# arm_driver.net
KiCad netlist of a schematic drawn in EAGLE
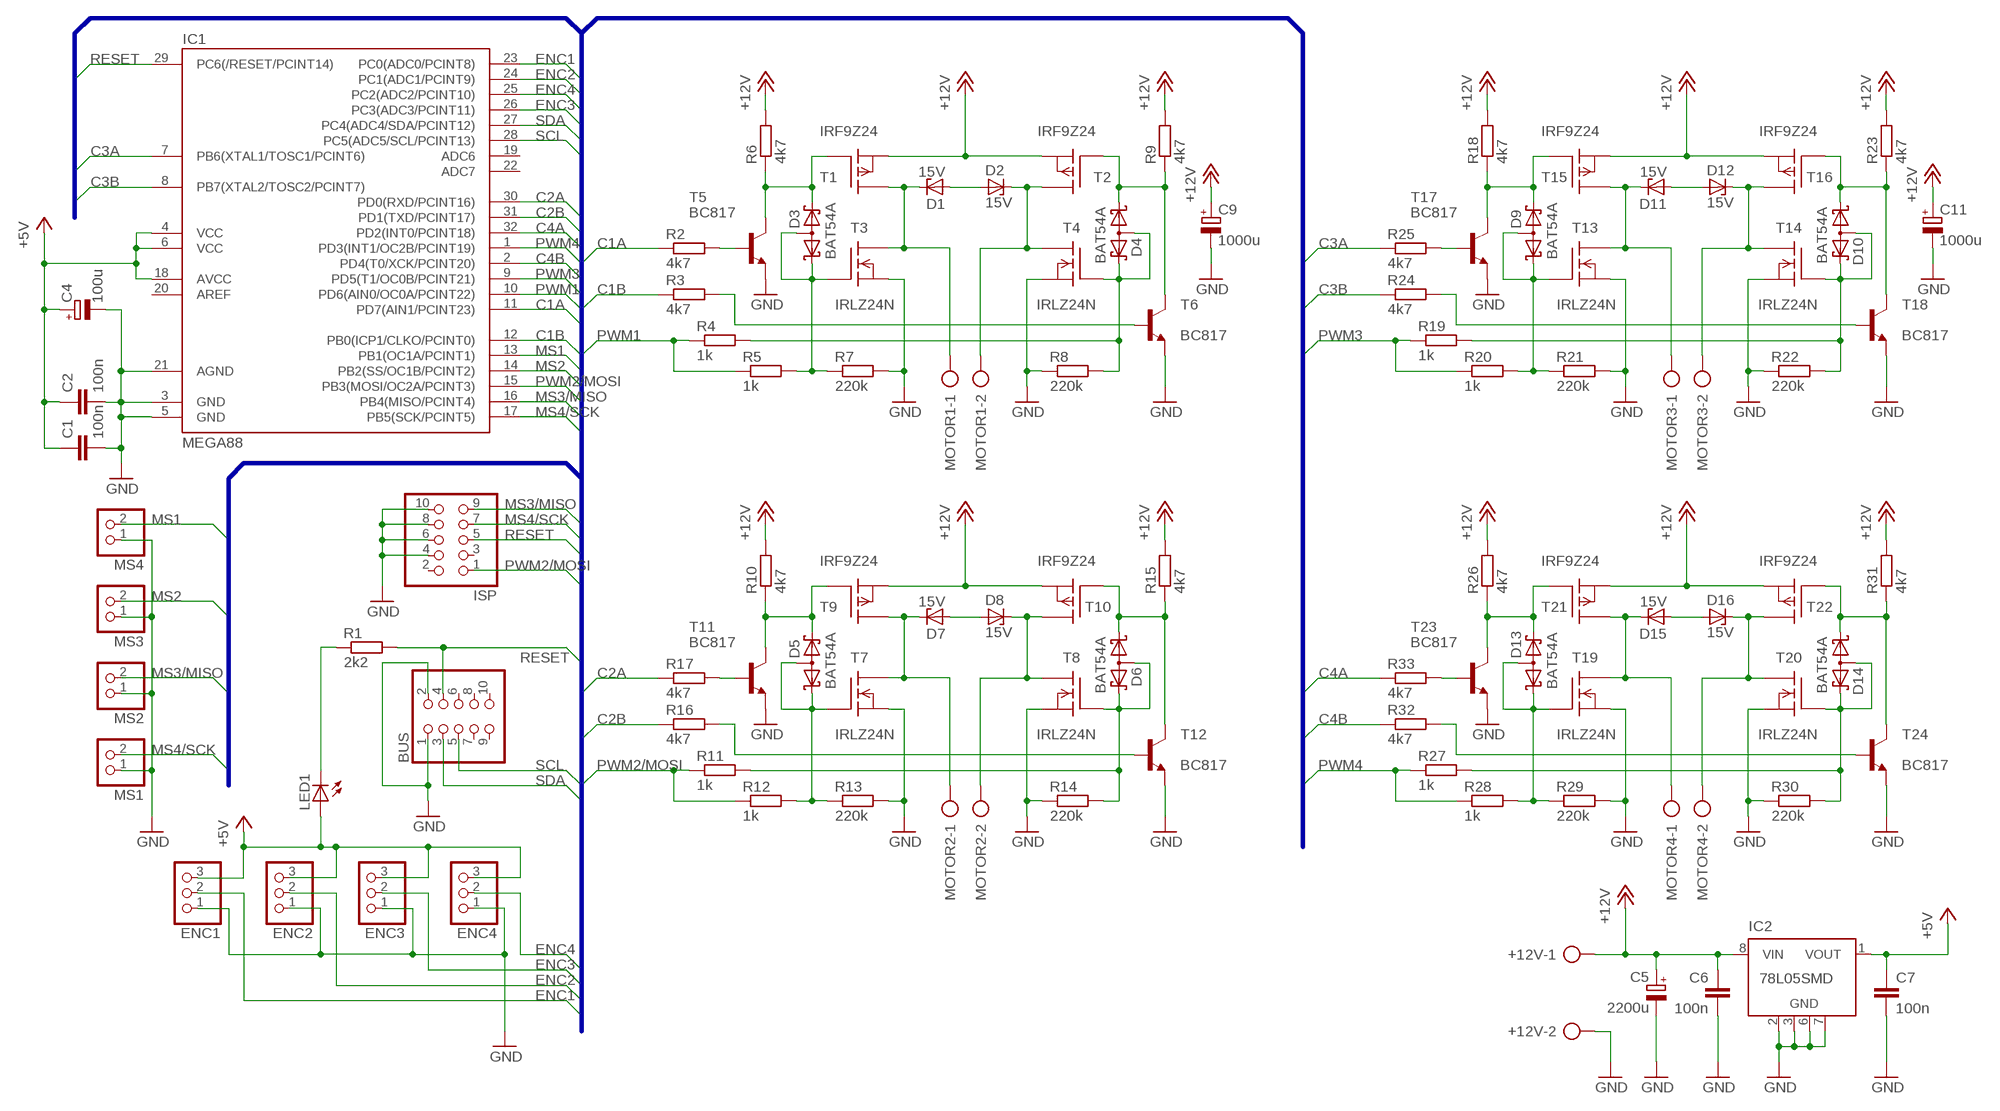
[diagram p0: schematic, sheet 1]

(export (version "E")
  (design (tool "Eeschema 10.0.6"))
  (components
    (comp (ref "+12V")
      (value "AK500/2")
      (footprint "eagle-import:AK500_2")
      (libsource (lib "eagle-import") (part "AK500/2"))
    )
    (comp (ref "BUS")
      (value "PINHD-2X5")
      (footprint "eagle-import:2X05")
      (libsource (lib "eagle-import") (part "PINHD-2X5"))
    )
    (comp (ref "C1")
      (value "100n")
      (footprint "eagle-import:C1206")
      (libsource (lib "eagle-import") (part "C-EUC1206"))
    )
    (comp (ref "C2")
      (value "100n")
      (footprint "eagle-import:C1206")
      (libsource (lib "eagle-import") (part "C-EUC1206"))
    )
    (comp (ref "C4")
      (value "100u")
      (footprint "eagle-import:D_7343-31R")
      (libsource (lib "eagle-import") (part "CPOL-EUD/7343-31R"))
    )
    (comp (ref "C5")
      (value "2200u")
      (footprint "eagle-import:E7,5-16")
      (libsource (lib "eagle-import") (part "CPOL-EUE7.5-16"))
    )
    (comp (ref "C6")
      (value "100n")
      (footprint "eagle-import:C1206")
      (libsource (lib "eagle-import") (part "C-EUC1206"))
    )
    (comp (ref "C7")
      (value "100n")
      (footprint "eagle-import:C1206")
      (libsource (lib "eagle-import") (part "C-EUC1206"))
    )
    (comp (ref "C9")
      (value "1000u")
      (footprint "eagle-import:E5-13")
      (libsource (lib "eagle-import") (part "CPOL-EUE5-13"))
    )
    (comp (ref "C11")
      (value "1000u")
      (footprint "eagle-import:E5-13")
      (libsource (lib "eagle-import") (part "CPOL-EUE5-13"))
    )
    (comp (ref "D1")
      (value "15V")
      (footprint "eagle-import:SOD80C")
      (libsource (lib "eagle-import") (part "ZENER-DIODESOD80C"))
    )
    (comp (ref "D2")
      (value "15V")
      (footprint "eagle-import:SOD80C")
      (libsource (lib "eagle-import") (part "ZENER-DIODESOD80C"))
    )
    (comp (ref "D3")
      (value "BAT54A")
      (footprint "eagle-import:SOT23")
      (libsource (lib "eagle-import") (part "BAT54A"))
    )
    (comp (ref "D4")
      (value "BAT54A")
      (footprint "eagle-import:SOT23")
      (libsource (lib "eagle-import") (part "BAT54A"))
    )
    (comp (ref "D5")
      (value "BAT54A")
      (footprint "eagle-import:SOT23")
      (libsource (lib "eagle-import") (part "BAT54A"))
    )
    (comp (ref "D6")
      (value "BAT54A")
      (footprint "eagle-import:SOT23")
      (libsource (lib "eagle-import") (part "BAT54A"))
    )
    (comp (ref "D7")
      (value "15V")
      (footprint "eagle-import:SOD80C")
      (libsource (lib "eagle-import") (part "ZENER-DIODESOD80C"))
    )
    (comp (ref "D8")
      (value "15V")
      (footprint "eagle-import:SOD80C")
      (libsource (lib "eagle-import") (part "ZENER-DIODESOD80C"))
    )
    (comp (ref "D9")
      (value "BAT54A")
      (footprint "eagle-import:SOT23")
      (libsource (lib "eagle-import") (part "BAT54A"))
    )
    (comp (ref "D10")
      (value "BAT54A")
      (footprint "eagle-import:SOT23")
      (libsource (lib "eagle-import") (part "BAT54A"))
    )
    (comp (ref "D11")
      (value "15V")
      (footprint "eagle-import:SOD80C")
      (libsource (lib "eagle-import") (part "ZENER-DIODESOD80C"))
    )
    (comp (ref "D12")
      (value "15V")
      (footprint "eagle-import:SOD80C")
      (libsource (lib "eagle-import") (part "ZENER-DIODESOD80C"))
    )
    (comp (ref "D13")
      (value "BAT54A")
      (footprint "eagle-import:SOT23")
      (libsource (lib "eagle-import") (part "BAT54A"))
    )
    (comp (ref "D14")
      (value "BAT54A")
      (footprint "eagle-import:SOT23")
      (libsource (lib "eagle-import") (part "BAT54A"))
    )
    (comp (ref "D15")
      (value "15V")
      (footprint "eagle-import:SOD80C")
      (libsource (lib "eagle-import") (part "ZENER-DIODESOD80C"))
    )
    (comp (ref "D16")
      (value "15V")
      (footprint "eagle-import:SOD80C")
      (libsource (lib "eagle-import") (part "ZENER-DIODESOD80C"))
    )
    (comp (ref "ENC1")
      (value "PINHD-1X3")
      (footprint "eagle-import:1X03")
      (libsource (lib "eagle-import") (part "PINHD-1X3"))
    )
    (comp (ref "ENC2")
      (value "PINHD-1X3")
      (footprint "eagle-import:1X03")
      (libsource (lib "eagle-import") (part "PINHD-1X3"))
    )
    (comp (ref "ENC3")
      (value "PINHD-1X3")
      (footprint "eagle-import:1X03")
      (libsource (lib "eagle-import") (part "PINHD-1X3"))
    )
    (comp (ref "ENC4")
      (value "PINHD-1X3")
      (footprint "eagle-import:1X03")
      (libsource (lib "eagle-import") (part "PINHD-1X3"))
    )
    (comp (ref "IC1")
      (value "MEGA88")
      (footprint "eagle-import:TQFP32-08")
      (libsource (lib "eagle-import") (part "MEGA48/88/168-AU"))
    )
    (comp (ref "IC2")
      (value "78L05SMD")
      (footprint "eagle-import:SO08")
      (libsource (lib "eagle-import") (part "78LSMD05"))
    )
    (comp (ref "ISP")
      (value "PINHD-2X5")
      (footprint "eagle-import:2X05")
      (libsource (lib "eagle-import") (part "PINHD-2X5"))
    )
    (comp (ref "LED1")
      (value "LEDKA-3528ASYC")
      (footprint "eagle-import:KA-3528ASYC")
      (libsource (lib "eagle-import") (part "LEDKA-3528ASYC"))
    )
    (comp (ref "MOTOR1")
      (value "AK500/2")
      (footprint "eagle-import:AK500_2")
      (libsource (lib "eagle-import") (part "AK500/2"))
    )
    (comp (ref "MOTOR2")
      (value "AK500/2")
      (footprint "eagle-import:AK500_2")
      (libsource (lib "eagle-import") (part "AK500/2"))
    )
    (comp (ref "MOTOR3")
      (value "AK500/2")
      (footprint "eagle-import:AK500_2")
      (libsource (lib "eagle-import") (part "AK500/2"))
    )
    (comp (ref "MOTOR4")
      (value "AK500/2")
      (footprint "eagle-import:AK500_2")
      (libsource (lib "eagle-import") (part "AK500/2"))
    )
    (comp (ref "MS1")
      (value "PINHD-1X2")
      (footprint "eagle-import:1X02")
      (libsource (lib "eagle-import") (part "PINHD-1X2"))
    )
    (comp (ref "MS2")
      (value "PINHD-1X2")
      (footprint "eagle-import:1X02")
      (libsource (lib "eagle-import") (part "PINHD-1X2"))
    )
    (comp (ref "MS3")
      (value "PINHD-1X2")
      (footprint "eagle-import:1X02")
      (libsource (lib "eagle-import") (part "PINHD-1X2"))
    )
    (comp (ref "MS4")
      (value "PINHD-1X2")
      (footprint "eagle-import:1X02")
      (libsource (lib "eagle-import") (part "PINHD-1X2"))
    )
    (comp (ref "R1")
      (value "2k2")
      (footprint "eagle-import:R1206")
      (libsource (lib "eagle-import") (part "R-EU_R1206"))
    )
    (comp (ref "R2")
      (value "4k7")
      (footprint "eagle-import:R1206")
      (libsource (lib "eagle-import") (part "R-EU_R1206"))
    )
    (comp (ref "R3")
      (value "4k7")
      (footprint "eagle-import:R1206")
      (libsource (lib "eagle-import") (part "R-EU_R1206"))
    )
    (comp (ref "R4")
      (value "1k")
      (footprint "eagle-import:R1206")
      (libsource (lib "eagle-import") (part "R-EU_R1206"))
    )
    (comp (ref "R5")
      (value "1k")
      (footprint "eagle-import:R1206")
      (libsource (lib "eagle-import") (part "R-EU_R1206"))
    )
    (comp (ref "R6")
      (value "4k7")
      (footprint "eagle-import:R1206")
      (libsource (lib "eagle-import") (part "R-EU_R1206"))
    )
    (comp (ref "R7")
      (value "220k")
      (footprint "eagle-import:R1206")
      (libsource (lib "eagle-import") (part "R-EU_R1206"))
    )
    (comp (ref "R8")
      (value "220k")
      (footprint "eagle-import:R1206")
      (libsource (lib "eagle-import") (part "R-EU_R1206"))
    )
    (comp (ref "R9")
      (value "4k7")
      (footprint "eagle-import:R1206")
      (libsource (lib "eagle-import") (part "R-EU_R1206"))
    )
    (comp (ref "R10")
      (value "4k7")
      (footprint "eagle-import:R1206")
      (libsource (lib "eagle-import") (part "R-EU_R1206"))
    )
    (comp (ref "R11")
      (value "1k")
      (footprint "eagle-import:R1206")
      (libsource (lib "eagle-import") (part "R-EU_R1206"))
    )
    (comp (ref "R12")
      (value "1k")
      (footprint "eagle-import:R1206")
      (libsource (lib "eagle-import") (part "R-EU_R1206"))
    )
    (comp (ref "R13")
      (value "220k")
      (footprint "eagle-import:R1206")
      (libsource (lib "eagle-import") (part "R-EU_R1206"))
    )
    (comp (ref "R14")
      (value "220k")
      (footprint "eagle-import:R1206")
      (libsource (lib "eagle-import") (part "R-EU_R1206"))
    )
    (comp (ref "R15")
      (value "4k7")
      (footprint "eagle-import:R1206")
      (libsource (lib "eagle-import") (part "R-EU_R1206"))
    )
    (comp (ref "R16")
      (value "4k7")
      (footprint "eagle-import:R1206")
      (libsource (lib "eagle-import") (part "R-EU_R1206"))
    )
    (comp (ref "R17")
      (value "4k7")
      (footprint "eagle-import:R1206")
      (libsource (lib "eagle-import") (part "R-EU_R1206"))
    )
    (comp (ref "R18")
      (value "4k7")
      (footprint "eagle-import:R1206")
      (libsource (lib "eagle-import") (part "R-EU_R1206"))
    )
    (comp (ref "R19")
      (value "1k")
      (footprint "eagle-import:R1206")
      (libsource (lib "eagle-import") (part "R-EU_R1206"))
    )
    (comp (ref "R20")
      (value "1k")
      (footprint "eagle-import:R1206")
      (libsource (lib "eagle-import") (part "R-EU_R1206"))
    )
    (comp (ref "R21")
      (value "220k")
      (footprint "eagle-import:R1206")
      (libsource (lib "eagle-import") (part "R-EU_R1206"))
    )
    (comp (ref "R22")
      (value "220k")
      (footprint "eagle-import:R1206")
      (libsource (lib "eagle-import") (part "R-EU_R1206"))
    )
    (comp (ref "R23")
      (value "4k7")
      (footprint "eagle-import:R1206")
      (libsource (lib "eagle-import") (part "R-EU_R1206"))
    )
    (comp (ref "R24")
      (value "4k7")
      (footprint "eagle-import:R1206")
      (libsource (lib "eagle-import") (part "R-EU_R1206"))
    )
    (comp (ref "R25")
      (value "4k7")
      (footprint "eagle-import:R1206")
      (libsource (lib "eagle-import") (part "R-EU_R1206"))
    )
    (comp (ref "R26")
      (value "4k7")
      (footprint "eagle-import:R1206")
      (libsource (lib "eagle-import") (part "R-EU_R1206"))
    )
    (comp (ref "R27")
      (value "1k")
      (footprint "eagle-import:R1206")
      (libsource (lib "eagle-import") (part "R-EU_R1206"))
    )
    (comp (ref "R28")
      (value "1k")
      (footprint "eagle-import:R1206")
      (libsource (lib "eagle-import") (part "R-EU_R1206"))
    )
    (comp (ref "R29")
      (value "220k")
      (footprint "eagle-import:R1206")
      (libsource (lib "eagle-import") (part "R-EU_R1206"))
    )
    (comp (ref "R30")
      (value "220k")
      (footprint "eagle-import:R1206")
      (libsource (lib "eagle-import") (part "R-EU_R1206"))
    )
    (comp (ref "R31")
      (value "4k7")
      (footprint "eagle-import:R1206")
      (libsource (lib "eagle-import") (part "R-EU_R1206"))
    )
    (comp (ref "R32")
      (value "4k7")
      (footprint "eagle-import:R1206")
      (libsource (lib "eagle-import") (part "R-EU_R1206"))
    )
    (comp (ref "R33")
      (value "4k7")
      (footprint "eagle-import:R1206")
      (libsource (lib "eagle-import") (part "R-EU_R1206"))
    )
    (comp (ref "T1")
      (value "IRF9Z24")
      (footprint "eagle-import:TO220")
      (libsource (lib "eagle-import") (part "IRF9530"))
    )
    (comp (ref "T2")
      (value "IRF9Z24")
      (footprint "eagle-import:TO220")
      (libsource (lib "eagle-import") (part "IRF9530"))
    )
    (comp (ref "T3")
      (value "IRLZ24N")
      (footprint "eagle-import:TO220")
      (libsource (lib "eagle-import") (part "IRF540"))
    )
    (comp (ref "T4")
      (value "IRLZ24N")
      (footprint "eagle-import:TO220")
      (libsource (lib "eagle-import") (part "IRF540"))
    )
    (comp (ref "T5")
      (value "BC817")
      (footprint "eagle-import:SOT23-BEC")
      (libsource (lib "eagle-import") (part "-NPN-SOT23-BECBC817-16"))
    )
    (comp (ref "T6")
      (value "BC817")
      (footprint "eagle-import:SOT23-BEC")
      (libsource (lib "eagle-import") (part "-NPN-SOT23-BECBC817-16"))
    )
    (comp (ref "T7")
      (value "IRLZ24N")
      (footprint "eagle-import:TO220")
      (libsource (lib "eagle-import") (part "IRF540"))
    )
    (comp (ref "T8")
      (value "IRLZ24N")
      (footprint "eagle-import:TO220")
      (libsource (lib "eagle-import") (part "IRF540"))
    )
    (comp (ref "T9")
      (value "IRF9Z24")
      (footprint "eagle-import:TO220")
      (libsource (lib "eagle-import") (part "IRF9530"))
    )
    (comp (ref "T10")
      (value "IRF9Z24")
      (footprint "eagle-import:TO220")
      (libsource (lib "eagle-import") (part "IRF9530"))
    )
    (comp (ref "T11")
      (value "BC817")
      (footprint "eagle-import:SOT23-BEC")
      (libsource (lib "eagle-import") (part "-NPN-SOT23-BECBC817-16"))
    )
    (comp (ref "T12")
      (value "BC817")
      (footprint "eagle-import:SOT23-BEC")
      (libsource (lib "eagle-import") (part "-NPN-SOT23-BECBC817-16"))
    )
    (comp (ref "T13")
      (value "IRLZ24N")
      (footprint "eagle-import:TO220")
      (libsource (lib "eagle-import") (part "IRF540"))
    )
    (comp (ref "T14")
      (value "IRLZ24N")
      (footprint "eagle-import:TO220")
      (libsource (lib "eagle-import") (part "IRF540"))
    )
    (comp (ref "T15")
      (value "IRF9Z24")
      (footprint "eagle-import:TO220")
      (libsource (lib "eagle-import") (part "IRF9530"))
    )
    (comp (ref "T16")
      (value "IRF9Z24")
      (footprint "eagle-import:TO220")
      (libsource (lib "eagle-import") (part "IRF9530"))
    )
    (comp (ref "T17")
      (value "BC817")
      (footprint "eagle-import:SOT23-BEC")
      (libsource (lib "eagle-import") (part "-NPN-SOT23-BECBC817-16"))
    )
    (comp (ref "T18")
      (value "BC817")
      (footprint "eagle-import:SOT23-BEC")
      (libsource (lib "eagle-import") (part "-NPN-SOT23-BECBC817-16"))
    )
    (comp (ref "T19")
      (value "IRLZ24N")
      (footprint "eagle-import:TO220")
      (libsource (lib "eagle-import") (part "IRF540"))
    )
    (comp (ref "T20")
      (value "IRLZ24N")
      (footprint "eagle-import:TO220")
      (libsource (lib "eagle-import") (part "IRF540"))
    )
    (comp (ref "T21")
      (value "IRF9Z24")
      (footprint "eagle-import:TO220")
      (libsource (lib "eagle-import") (part "IRF9530"))
    )
    (comp (ref "T22")
      (value "IRF9Z24")
      (footprint "eagle-import:TO220")
      (libsource (lib "eagle-import") (part "IRF9530"))
    )
    (comp (ref "T23")
      (value "BC817")
      (footprint "eagle-import:SOT23-BEC")
      (libsource (lib "eagle-import") (part "-NPN-SOT23-BECBC817-16"))
    )
    (comp (ref "T24")
      (value "BC817")
      (footprint "eagle-import:SOT23-BEC")
      (libsource (lib "eagle-import") (part "-NPN-SOT23-BECBC817-16"))
    )
  )
  (nets
    (net (code "1") (name "+5V") (class "Default")
      (node (ref "C1") (pin "1") (pinfunction "1_1") (pintype "passive"))
      (node (ref "C2") (pin "1") (pinfunction "1_1") (pintype "passive"))
      (node (ref "C4") (pin "+") (pinfunction "+_+") (pintype "passive"))
      (node (ref "C7") (pin "1") (pinfunction "1_1") (pintype "passive"))
      (node (ref "ENC1") (pin "3") (pinfunction "3_3") (pintype "passive"))
      (node (ref "ENC2") (pin "3") (pinfunction "3_3") (pintype "passive"))
      (node (ref "ENC3") (pin "3") (pinfunction "3_3") (pintype "passive"))
      (node (ref "ENC4") (pin "3") (pinfunction "3_3") (pintype "passive"))
      (node (ref "IC1") (pin "18") (pinfunction "AVCC_18") (pintype "passive"))
      (node (ref "IC1") (pin "4") (pinfunction "VCC_4") (pintype "power_in"))
      (node (ref "IC1") (pin "6") (pinfunction "VCC_6") (pintype "power_in"))
      (node (ref "IC2") (pin "1") (pinfunction "VOUT_1") (pintype "output"))
      (node (ref "LED1") (pin "A") (pinfunction "A_A") (pintype "passive"))
    )
    (net (code "2") (name "+12V") (class "Default")
      (node (ref "+12V") (pin "1") (pinfunction "KL_1") (pintype "passive"))
      (node (ref "C11") (pin "+") (pinfunction "+_+") (pintype "passive"))
      (node (ref "C5") (pin "+") (pinfunction "+_+") (pintype "passive"))
      (node (ref "C6") (pin "1") (pinfunction "1_1") (pintype "passive"))
      (node (ref "C9") (pin "+") (pinfunction "+_+") (pintype "passive"))
      (node (ref "IC2") (pin "8") (pinfunction "VIN_8") (pintype "passive"))
      (node (ref "R10") (pin "2") (pinfunction "2_2") (pintype "passive"))
      (node (ref "R15") (pin "2") (pinfunction "2_2") (pintype "passive"))
      (node (ref "R18") (pin "2") (pinfunction "2_2") (pintype "passive"))
      (node (ref "R23") (pin "2") (pinfunction "2_2") (pintype "passive"))
      (node (ref "R26") (pin "2") (pinfunction "2_2") (pintype "passive"))
      (node (ref "R31") (pin "2") (pinfunction "2_2") (pintype "passive"))
      (node (ref "R6") (pin "2") (pinfunction "2_2") (pintype "passive"))
      (node (ref "R9") (pin "2") (pinfunction "2_2") (pintype "passive"))
      (node (ref "T1") (pin "3") (pinfunction "S_3") (pintype "passive"))
      (node (ref "T10") (pin "3") (pinfunction "S_3") (pintype "passive"))
      (node (ref "T15") (pin "3") (pinfunction "S_3") (pintype "passive"))
      (node (ref "T16") (pin "3") (pinfunction "S_3") (pintype "passive"))
      (node (ref "T2") (pin "3") (pinfunction "S_3") (pintype "passive"))
      (node (ref "T21") (pin "3") (pinfunction "S_3") (pintype "passive"))
      (node (ref "T22") (pin "3") (pinfunction "S_3") (pintype "passive"))
      (node (ref "T9") (pin "3") (pinfunction "S_3") (pintype "passive"))
    )
    (net (code "3") (name "/C1A") (class "Default")
      (node (ref "IC1") (pin "11") (pinfunction "PD7(AIN1/PCINT23)_11") (pintype "bidirectional"))
      (node (ref "R2") (pin "1") (pinfunction "1_1") (pintype "passive"))
    )
    (net (code "4") (name "/C1B") (class "Default")
      (node (ref "IC1") (pin "12") (pinfunction "PB0(ICP1/CLKO/PCINT0)_12") (pintype "bidirectional"))
      (node (ref "R3") (pin "1") (pinfunction "1_1") (pintype "passive"))
    )
    (net (code "5") (name "/C2A") (class "Default")
      (node (ref "IC1") (pin "30") (pinfunction "PD0(RXD/PCINT16)_30") (pintype "bidirectional"))
      (node (ref "R17") (pin "1") (pinfunction "1_1") (pintype "passive"))
    )
    (net (code "6") (name "/C2B") (class "Default")
      (node (ref "IC1") (pin "31") (pinfunction "PD1(TXD/PCINT17)_31") (pintype "bidirectional"))
      (node (ref "R16") (pin "1") (pinfunction "1_1") (pintype "passive"))
    )
    (net (code "7") (name "/C3A") (class "Default")
      (node (ref "IC1") (pin "7") (pinfunction "PB6(XTAL1/TOSC1/PCINT6)_7") (pintype "bidirectional"))
      (node (ref "R25") (pin "1") (pinfunction "1_1") (pintype "passive"))
    )
    (net (code "8") (name "/C3B") (class "Default")
      (node (ref "IC1") (pin "8") (pinfunction "PB7(XTAL2/TOSC2/PCINT7)_8") (pintype "bidirectional"))
      (node (ref "R24") (pin "1") (pinfunction "1_1") (pintype "passive"))
    )
    (net (code "9") (name "/C4A") (class "Default")
      (node (ref "IC1") (pin "32") (pinfunction "PD2(INT0/PCINT18)_32") (pintype "bidirectional"))
      (node (ref "R33") (pin "1") (pinfunction "1_1") (pintype "passive"))
    )
    (net (code "10") (name "/C4B") (class "Default")
      (node (ref "IC1") (pin "2") (pinfunction "PD4(T0/XCK/PCINT20)_2") (pintype "bidirectional"))
      (node (ref "R32") (pin "1") (pinfunction "1_1") (pintype "passive"))
    )
    (net (code "11") (name "/ENC1") (class "Default")
      (node (ref "ENC1") (pin "2") (pinfunction "2_2") (pintype "passive"))
      (node (ref "IC1") (pin "23") (pinfunction "PC0(ADC0/PCINT8)_23") (pintype "bidirectional"))
    )
    (net (code "12") (name "/ENC2") (class "Default")
      (node (ref "ENC2") (pin "2") (pinfunction "2_2") (pintype "passive"))
      (node (ref "IC1") (pin "24") (pinfunction "PC1(ADC1/PCINT9)_24") (pintype "bidirectional"))
    )
    (net (code "13") (name "/ENC3") (class "Default")
      (node (ref "ENC3") (pin "2") (pinfunction "2_2") (pintype "passive"))
      (node (ref "IC1") (pin "26") (pinfunction "PC3(ADC3/PCINT11)_26") (pintype "bidirectional"))
    )
    (net (code "14") (name "/ENC4") (class "Default")
      (node (ref "ENC4") (pin "2") (pinfunction "2_2") (pintype "passive"))
      (node (ref "IC1") (pin "25") (pinfunction "PC2(ADC2/PCINT10)_25") (pintype "bidirectional"))
    )
    (net (code "15") (name "/MS1") (class "Default")
      (node (ref "IC1") (pin "13") (pinfunction "PB1(OC1A/PCINT1)_13") (pintype "bidirectional"))
      (node (ref "MS4") (pin "2") (pinfunction "2_2") (pintype "passive"))
    )
    (net (code "16") (name "/MS2") (class "Default")
      (node (ref "IC1") (pin "14") (pinfunction "PB2(SS/OC1B/PCINT2)_14") (pintype "bidirectional"))
      (node (ref "MS3") (pin "2") (pinfunction "2_2") (pintype "passive"))
    )
    (net (code "17") (name "/MS3{slash}MISO") (class "Default")
      (node (ref "IC1") (pin "16") (pinfunction "PB4(MISO/PCINT4)_16") (pintype "bidirectional"))
      (node (ref "ISP") (pin "9") (pinfunction "9_9") (pintype "passive"))
      (node (ref "MS2") (pin "2") (pinfunction "2_2") (pintype "passive"))
    )
    (net (code "18") (name "/MS4{slash}SCK") (class "Default")
      (node (ref "IC1") (pin "17") (pinfunction "PB5(SCK/PCINT5)_17") (pintype "bidirectional"))
      (node (ref "ISP") (pin "7") (pinfunction "7_7") (pintype "passive"))
      (node (ref "MS1") (pin "2") (pinfunction "2_2") (pintype "passive"))
    )
    (net (code "19") (name "/PWM1") (class "Default")
      (node (ref "IC1") (pin "10") (pinfunction "PD6(AIN0/OC0A/PCINT22)_10") (pintype "bidirectional"))
      (node (ref "R4") (pin "1") (pinfunction "1_1") (pintype "passive"))
      (node (ref "R5") (pin "1") (pinfunction "1_1") (pintype "passive"))
    )
    (net (code "20") (name "/PWM2{slash}MOSI") (class "Default")
      (node (ref "IC1") (pin "15") (pinfunction "PB3(MOSI/OC2A/PCINT3)_15") (pintype "bidirectional"))
      (node (ref "ISP") (pin "1") (pinfunction "1_1") (pintype "passive"))
      (node (ref "R11") (pin "1") (pinfunction "1_1") (pintype "passive"))
      (node (ref "R12") (pin "1") (pinfunction "1_1") (pintype "passive"))
    )
    (net (code "21") (name "/PWM3") (class "Default")
      (node (ref "IC1") (pin "9") (pinfunction "PD5(T1/OC0B/PCINT21)_9") (pintype "bidirectional"))
      (node (ref "R19") (pin "1") (pinfunction "1_1") (pintype "passive"))
      (node (ref "R20") (pin "1") (pinfunction "1_1") (pintype "passive"))
    )
    (net (code "22") (name "/PWM4") (class "Default")
      (node (ref "IC1") (pin "1") (pinfunction "PD3(INT1/OC2B/PCINT19)_1") (pintype "bidirectional"))
      (node (ref "R27") (pin "1") (pinfunction "1_1") (pintype "passive"))
      (node (ref "R28") (pin "1") (pinfunction "1_1") (pintype "passive"))
    )
    (net (code "23") (name "/RESET") (class "Default")
      (node (ref "BUS") (pin "4") (pinfunction "4_4") (pintype "passive"))
      (node (ref "IC1") (pin "29") (pinfunction "PC6(/RESET/PCINT14)_29") (pintype "bidirectional"))
      (node (ref "ISP") (pin "5") (pinfunction "5_5") (pintype "passive"))
      (node (ref "R1") (pin "2") (pinfunction "2_2") (pintype "passive"))
    )
    (net (code "24") (name "/SCL") (class "Default")
      (node (ref "BUS") (pin "5") (pinfunction "5_5") (pintype "passive"))
      (node (ref "IC1") (pin "28") (pinfunction "PC5(ADC5/SCL/PCINT13)_28") (pintype "bidirectional"))
    )
    (net (code "25") (name "/SDA") (class "Default")
      (node (ref "BUS") (pin "3") (pinfunction "3_3") (pintype "passive"))
      (node (ref "IC1") (pin "27") (pinfunction "PC4(ADC4/SDA/PCINT12)_27") (pintype "bidirectional"))
    )
    (net (code "26") (name "GND") (class "Default")
      (node (ref "+12V") (pin "2") (pinfunction "KL_2") (pintype "passive"))
      (node (ref "BUS") (pin "1") (pinfunction "1_1") (pintype "passive"))
      (node (ref "BUS") (pin "2") (pinfunction "2_2") (pintype "passive"))
      (node (ref "C1") (pin "2") (pinfunction "2_2") (pintype "passive"))
      (node (ref "C11") (pin "-") (pinfunction "-_-") (pintype "passive"))
      (node (ref "C2") (pin "2") (pinfunction "2_2") (pintype "passive"))
      (node (ref "C4") (pin "-") (pinfunction "-_-") (pintype "passive"))
      (node (ref "C5") (pin "-") (pinfunction "-_-") (pintype "passive"))
      (node (ref "C6") (pin "2") (pinfunction "2_2") (pintype "passive"))
      (node (ref "C7") (pin "2") (pinfunction "2_2") (pintype "passive"))
      (node (ref "C9") (pin "-") (pinfunction "-_-") (pintype "passive"))
      (node (ref "ENC1") (pin "1") (pinfunction "1_1") (pintype "passive"))
      (node (ref "ENC2") (pin "1") (pinfunction "1_1") (pintype "passive"))
      (node (ref "ENC3") (pin "1") (pinfunction "1_1") (pintype "passive"))
      (node (ref "ENC4") (pin "1") (pinfunction "1_1") (pintype "passive"))
      (node (ref "IC1") (pin "21") (pinfunction "AGND_21") (pintype "power_in"))
      (node (ref "IC1") (pin "3") (pinfunction "GND_3") (pintype "power_in"))
      (node (ref "IC1") (pin "5") (pinfunction "GND_5") (pintype "power_in"))
      (node (ref "IC2") (pin "2") (pinfunction "GND_2") (pintype "power_in"))
      (node (ref "IC2") (pin "3") (pinfunction "GND_3") (pintype "power_in"))
      (node (ref "IC2") (pin "6") (pinfunction "GND_6") (pintype "power_in"))
      (node (ref "IC2") (pin "7") (pinfunction "GND_7") (pintype "power_in"))
      (node (ref "ISP") (pin "10") (pinfunction "10_10") (pintype "passive"))
      (node (ref "ISP") (pin "4") (pinfunction "4_4") (pintype "passive"))
      (node (ref "ISP") (pin "6") (pinfunction "6_6") (pintype "passive"))
      (node (ref "ISP") (pin "8") (pinfunction "8_8") (pintype "passive"))
      (node (ref "MS1") (pin "1") (pinfunction "1_1") (pintype "passive"))
      (node (ref "MS2") (pin "1") (pinfunction "1_1") (pintype "passive"))
      (node (ref "MS3") (pin "1") (pinfunction "1_1") (pintype "passive"))
      (node (ref "MS4") (pin "1") (pinfunction "1_1") (pintype "passive"))
      (node (ref "R13") (pin "2") (pinfunction "2_2") (pintype "passive"))
      (node (ref "R14") (pin "1") (pinfunction "1_1") (pintype "passive"))
      (node (ref "R21") (pin "2") (pinfunction "2_2") (pintype "passive"))
      (node (ref "R22") (pin "1") (pinfunction "1_1") (pintype "passive"))
      (node (ref "R29") (pin "2") (pinfunction "2_2") (pintype "passive"))
      (node (ref "R30") (pin "1") (pinfunction "1_1") (pintype "passive"))
      (node (ref "R7") (pin "2") (pinfunction "2_2") (pintype "passive"))
      (node (ref "R8") (pin "1") (pinfunction "1_1") (pintype "passive"))
      (node (ref "T11") (pin "E") (pinfunction "E_E") (pintype "passive"))
      (node (ref "T12") (pin "E") (pinfunction "E_E") (pintype "passive"))
      (node (ref "T13") (pin "3") (pinfunction "S_3") (pintype "passive"))
      (node (ref "T14") (pin "3") (pinfunction "S_3") (pintype "passive"))
      (node (ref "T17") (pin "E") (pinfunction "E_E") (pintype "passive"))
      (node (ref "T18") (pin "E") (pinfunction "E_E") (pintype "passive"))
      (node (ref "T19") (pin "3") (pinfunction "S_3") (pintype "passive"))
      (node (ref "T20") (pin "3") (pinfunction "S_3") (pintype "passive"))
      (node (ref "T23") (pin "E") (pinfunction "E_E") (pintype "passive"))
      (node (ref "T24") (pin "E") (pinfunction "E_E") (pintype "passive"))
      (node (ref "T3") (pin "3") (pinfunction "S_3") (pintype "passive"))
      (node (ref "T4") (pin "3") (pinfunction "S_3") (pintype "passive"))
      (node (ref "T5") (pin "E") (pinfunction "E_E") (pintype "passive"))
      (node (ref "T6") (pin "E") (pinfunction "E_E") (pintype "passive"))
      (node (ref "T7") (pin "3") (pinfunction "S_3") (pintype "passive"))
      (node (ref "T8") (pin "3") (pinfunction "S_3") (pintype "passive"))
    )
    (net (code "27") (name "Net-(D1-PadA)") (class "Default")
      (node (ref "D1") (pin "A") (pinfunction "A_A") (pintype "passive"))
      (node (ref "D2") (pin "A") (pinfunction "A_A") (pintype "passive"))
    )
    (net (code "28") (name "Net-(D3-AA)") (class "Default")
      (node (ref "D3") (pin "1") (pinfunction "K1_1") (pintype "passive"))
      (node (ref "D3") (pin "3") (pinfunction "AA_3") (pintype "passive"))
      (node (ref "R5") (pin "2") (pinfunction "2_2") (pintype "passive"))
      (node (ref "R7") (pin "1") (pinfunction "1_1") (pintype "passive"))
      (node (ref "T3") (pin "1") (pinfunction "G_1") (pintype "passive"))
    )
    (net (code "29") (name "Net-(D3-K2)") (class "Default")
      (node (ref "D3") (pin "2") (pinfunction "K2_2") (pintype "passive"))
      (node (ref "R6") (pin "1") (pinfunction "1_1") (pintype "passive"))
      (node (ref "T1") (pin "1") (pinfunction "G_1") (pintype "passive"))
      (node (ref "T5") (pin "C") (pinfunction "C_C") (pintype "passive"))
    )
    (net (code "30") (name "Net-(D4-AA)") (class "Default")
      (node (ref "D4") (pin "2") (pinfunction "K2_2") (pintype "passive"))
      (node (ref "D4") (pin "3") (pinfunction "AA_3") (pintype "passive"))
      (node (ref "R4") (pin "2") (pinfunction "2_2") (pintype "passive"))
      (node (ref "R8") (pin "2") (pinfunction "2_2") (pintype "passive"))
      (node (ref "T4") (pin "1") (pinfunction "G_1") (pintype "passive"))
    )
    (net (code "31") (name "Net-(D4-K1)") (class "Default")
      (node (ref "D4") (pin "1") (pinfunction "K1_1") (pintype "passive"))
      (node (ref "R9") (pin "1") (pinfunction "1_1") (pintype "passive"))
      (node (ref "T2") (pin "1") (pinfunction "G_1") (pintype "passive"))
      (node (ref "T6") (pin "C") (pinfunction "C_C") (pintype "passive"))
    )
    (net (code "32") (name "Net-(D5-AA)") (class "Default")
      (node (ref "D5") (pin "1") (pinfunction "K1_1") (pintype "passive"))
      (node (ref "D5") (pin "3") (pinfunction "AA_3") (pintype "passive"))
      (node (ref "R12") (pin "2") (pinfunction "2_2") (pintype "passive"))
      (node (ref "R13") (pin "1") (pinfunction "1_1") (pintype "passive"))
      (node (ref "T7") (pin "1") (pinfunction "G_1") (pintype "passive"))
    )
    (net (code "33") (name "Net-(D5-K2)") (class "Default")
      (node (ref "D5") (pin "2") (pinfunction "K2_2") (pintype "passive"))
      (node (ref "R10") (pin "1") (pinfunction "1_1") (pintype "passive"))
      (node (ref "T11") (pin "C") (pinfunction "C_C") (pintype "passive"))
      (node (ref "T9") (pin "1") (pinfunction "G_1") (pintype "passive"))
    )
    (net (code "34") (name "Net-(D6-AA)") (class "Default")
      (node (ref "D6") (pin "2") (pinfunction "K2_2") (pintype "passive"))
      (node (ref "D6") (pin "3") (pinfunction "AA_3") (pintype "passive"))
      (node (ref "R11") (pin "2") (pinfunction "2_2") (pintype "passive"))
      (node (ref "R14") (pin "2") (pinfunction "2_2") (pintype "passive"))
      (node (ref "T8") (pin "1") (pinfunction "G_1") (pintype "passive"))
    )
    (net (code "35") (name "Net-(D6-K1)") (class "Default")
      (node (ref "D6") (pin "1") (pinfunction "K1_1") (pintype "passive"))
      (node (ref "R15") (pin "1") (pinfunction "1_1") (pintype "passive"))
      (node (ref "T10") (pin "1") (pinfunction "G_1") (pintype "passive"))
      (node (ref "T12") (pin "C") (pinfunction "C_C") (pintype "passive"))
    )
    (net (code "36") (name "Net-(D7-PadA)") (class "Default")
      (node (ref "D7") (pin "A") (pinfunction "A_A") (pintype "passive"))
      (node (ref "D8") (pin "A") (pinfunction "A_A") (pintype "passive"))
    )
    (net (code "37") (name "Net-(D9-AA)") (class "Default")
      (node (ref "D9") (pin "1") (pinfunction "K1_1") (pintype "passive"))
      (node (ref "D9") (pin "3") (pinfunction "AA_3") (pintype "passive"))
      (node (ref "R20") (pin "2") (pinfunction "2_2") (pintype "passive"))
      (node (ref "R21") (pin "1") (pinfunction "1_1") (pintype "passive"))
      (node (ref "T13") (pin "1") (pinfunction "G_1") (pintype "passive"))
    )
    (net (code "38") (name "Net-(D9-K2)") (class "Default")
      (node (ref "D9") (pin "2") (pinfunction "K2_2") (pintype "passive"))
      (node (ref "R18") (pin "1") (pinfunction "1_1") (pintype "passive"))
      (node (ref "T15") (pin "1") (pinfunction "G_1") (pintype "passive"))
      (node (ref "T17") (pin "C") (pinfunction "C_C") (pintype "passive"))
    )
    (net (code "39") (name "Net-(D10-AA)") (class "Default")
      (node (ref "D10") (pin "2") (pinfunction "K2_2") (pintype "passive"))
      (node (ref "D10") (pin "3") (pinfunction "AA_3") (pintype "passive"))
      (node (ref "R19") (pin "2") (pinfunction "2_2") (pintype "passive"))
      (node (ref "R22") (pin "2") (pinfunction "2_2") (pintype "passive"))
      (node (ref "T14") (pin "1") (pinfunction "G_1") (pintype "passive"))
    )
    (net (code "40") (name "Net-(D10-K1)") (class "Default")
      (node (ref "D10") (pin "1") (pinfunction "K1_1") (pintype "passive"))
      (node (ref "R23") (pin "1") (pinfunction "1_1") (pintype "passive"))
      (node (ref "T16") (pin "1") (pinfunction "G_1") (pintype "passive"))
      (node (ref "T18") (pin "C") (pinfunction "C_C") (pintype "passive"))
    )
    (net (code "41") (name "Net-(D11-PadA)") (class "Default")
      (node (ref "D11") (pin "A") (pinfunction "A_A") (pintype "passive"))
      (node (ref "D12") (pin "A") (pinfunction "A_A") (pintype "passive"))
    )
    (net (code "42") (name "Net-(D13-AA)") (class "Default")
      (node (ref "D13") (pin "1") (pinfunction "K1_1") (pintype "passive"))
      (node (ref "D13") (pin "3") (pinfunction "AA_3") (pintype "passive"))
      (node (ref "R28") (pin "2") (pinfunction "2_2") (pintype "passive"))
      (node (ref "R29") (pin "1") (pinfunction "1_1") (pintype "passive"))
      (node (ref "T19") (pin "1") (pinfunction "G_1") (pintype "passive"))
    )
    (net (code "43") (name "Net-(D13-K2)") (class "Default")
      (node (ref "D13") (pin "2") (pinfunction "K2_2") (pintype "passive"))
      (node (ref "R26") (pin "1") (pinfunction "1_1") (pintype "passive"))
      (node (ref "T21") (pin "1") (pinfunction "G_1") (pintype "passive"))
      (node (ref "T23") (pin "C") (pinfunction "C_C") (pintype "passive"))
    )
    (net (code "44") (name "Net-(D14-AA)") (class "Default")
      (node (ref "D14") (pin "2") (pinfunction "K2_2") (pintype "passive"))
      (node (ref "D14") (pin "3") (pinfunction "AA_3") (pintype "passive"))
      (node (ref "R27") (pin "2") (pinfunction "2_2") (pintype "passive"))
      (node (ref "R30") (pin "2") (pinfunction "2_2") (pintype "passive"))
      (node (ref "T20") (pin "1") (pinfunction "G_1") (pintype "passive"))
    )
    (net (code "45") (name "Net-(D14-K1)") (class "Default")
      (node (ref "D14") (pin "1") (pinfunction "K1_1") (pintype "passive"))
      (node (ref "R31") (pin "1") (pinfunction "1_1") (pintype "passive"))
      (node (ref "T22") (pin "1") (pinfunction "G_1") (pintype "passive"))
      (node (ref "T24") (pin "C") (pinfunction "C_C") (pintype "passive"))
    )
    (net (code "46") (name "Net-(D15-PadA)") (class "Default")
      (node (ref "D15") (pin "A") (pinfunction "A_A") (pintype "passive"))
      (node (ref "D16") (pin "A") (pinfunction "A_A") (pintype "passive"))
    )
    (net (code "47") (name "Net-(LED1-PadC)") (class "Default")
      (node (ref "LED1") (pin "C") (pinfunction "C_C") (pintype "passive"))
      (node (ref "R1") (pin "1") (pinfunction "1_1") (pintype "passive"))
    )
    (net (code "48") (name "Net-(MOTOR1A-KL)") (class "Default")
      (node (ref "D1") (pin "C") (pinfunction "C_C") (pintype "passive"))
      (node (ref "MOTOR1") (pin "1") (pinfunction "KL_1") (pintype "passive"))
      (node (ref "T1") (pin "2") (pinfunction "D_2") (pintype "passive"))
      (node (ref "T3") (pin "2") (pinfunction "D_2") (pintype "passive"))
    )
    (net (code "49") (name "Net-(MOTOR1B-KL)") (class "Default")
      (node (ref "D2") (pin "C") (pinfunction "C_C") (pintype "passive"))
      (node (ref "MOTOR1") (pin "2") (pinfunction "KL_2") (pintype "passive"))
      (node (ref "T2") (pin "2") (pinfunction "D_2") (pintype "passive"))
      (node (ref "T4") (pin "2") (pinfunction "D_2") (pintype "passive"))
    )
    (net (code "50") (name "Net-(MOTOR2A-KL)") (class "Default")
      (node (ref "D7") (pin "C") (pinfunction "C_C") (pintype "passive"))
      (node (ref "MOTOR2") (pin "1") (pinfunction "KL_1") (pintype "passive"))
      (node (ref "T7") (pin "2") (pinfunction "D_2") (pintype "passive"))
      (node (ref "T9") (pin "2") (pinfunction "D_2") (pintype "passive"))
    )
    (net (code "51") (name "Net-(MOTOR2B-KL)") (class "Default")
      (node (ref "D8") (pin "C") (pinfunction "C_C") (pintype "passive"))
      (node (ref "MOTOR2") (pin "2") (pinfunction "KL_2") (pintype "passive"))
      (node (ref "T10") (pin "2") (pinfunction "D_2") (pintype "passive"))
      (node (ref "T8") (pin "2") (pinfunction "D_2") (pintype "passive"))
    )
    (net (code "52") (name "Net-(MOTOR3A-KL)") (class "Default")
      (node (ref "D11") (pin "C") (pinfunction "C_C") (pintype "passive"))
      (node (ref "MOTOR3") (pin "1") (pinfunction "KL_1") (pintype "passive"))
      (node (ref "T13") (pin "2") (pinfunction "D_2") (pintype "passive"))
      (node (ref "T15") (pin "2") (pinfunction "D_2") (pintype "passive"))
    )
    (net (code "53") (name "Net-(MOTOR3B-KL)") (class "Default")
      (node (ref "D12") (pin "C") (pinfunction "C_C") (pintype "passive"))
      (node (ref "MOTOR3") (pin "2") (pinfunction "KL_2") (pintype "passive"))
      (node (ref "T14") (pin "2") (pinfunction "D_2") (pintype "passive"))
      (node (ref "T16") (pin "2") (pinfunction "D_2") (pintype "passive"))
    )
    (net (code "54") (name "Net-(MOTOR4A-KL)") (class "Default")
      (node (ref "D15") (pin "C") (pinfunction "C_C") (pintype "passive"))
      (node (ref "MOTOR4") (pin "1") (pinfunction "KL_1") (pintype "passive"))
      (node (ref "T19") (pin "2") (pinfunction "D_2") (pintype "passive"))
      (node (ref "T21") (pin "2") (pinfunction "D_2") (pintype "passive"))
    )
    (net (code "55") (name "Net-(MOTOR4B-KL)") (class "Default")
      (node (ref "D16") (pin "C") (pinfunction "C_C") (pintype "passive"))
      (node (ref "MOTOR4") (pin "2") (pinfunction "KL_2") (pintype "passive"))
      (node (ref "T20") (pin "2") (pinfunction "D_2") (pintype "passive"))
      (node (ref "T22") (pin "2") (pinfunction "D_2") (pintype "passive"))
    )
    (net (code "56") (name "Net-(R2-Pad2)") (class "Default")
      (node (ref "R2") (pin "2") (pinfunction "2_2") (pintype "passive"))
      (node (ref "T5") (pin "B") (pinfunction "B_B") (pintype "passive"))
    )
    (net (code "57") (name "Net-(R3-Pad2)") (class "Default")
      (node (ref "R3") (pin "2") (pinfunction "2_2") (pintype "passive"))
      (node (ref "T6") (pin "B") (pinfunction "B_B") (pintype "passive"))
    )
    (net (code "58") (name "Net-(R16-Pad2)") (class "Default")
      (node (ref "R16") (pin "2") (pinfunction "2_2") (pintype "passive"))
      (node (ref "T12") (pin "B") (pinfunction "B_B") (pintype "passive"))
    )
    (net (code "59") (name "Net-(R17-Pad2)") (class "Default")
      (node (ref "R17") (pin "2") (pinfunction "2_2") (pintype "passive"))
      (node (ref "T11") (pin "B") (pinfunction "B_B") (pintype "passive"))
    )
    (net (code "60") (name "Net-(R24-Pad2)") (class "Default")
      (node (ref "R24") (pin "2") (pinfunction "2_2") (pintype "passive"))
      (node (ref "T18") (pin "B") (pinfunction "B_B") (pintype "passive"))
    )
    (net (code "61") (name "Net-(R25-Pad2)") (class "Default")
      (node (ref "R25") (pin "2") (pinfunction "2_2") (pintype "passive"))
      (node (ref "T17") (pin "B") (pinfunction "B_B") (pintype "passive"))
    )
    (net (code "62") (name "Net-(R32-Pad2)") (class "Default")
      (node (ref "R32") (pin "2") (pinfunction "2_2") (pintype "passive"))
      (node (ref "T24") (pin "B") (pinfunction "B_B") (pintype "passive"))
    )
    (net (code "63") (name "Net-(R33-Pad2)") (class "Default")
      (node (ref "R33") (pin "2") (pinfunction "2_2") (pintype "passive"))
      (node (ref "T23") (pin "B") (pinfunction "B_B") (pintype "passive"))
    )
    (net (code "64") (name "unconnected-(BUS-Pad6)") (class "Default")
      (node (ref "BUS") (pin "6") (pinfunction "6_6") (pintype "passive"))
    )
    (net (code "65") (name "unconnected-(BUS-Pad7)") (class "Default")
      (node (ref "BUS") (pin "7") (pinfunction "7_7") (pintype "passive"))
    )
    (net (code "66") (name "unconnected-(BUS-Pad8)") (class "Default")
      (node (ref "BUS") (pin "8") (pinfunction "8_8") (pintype "passive"))
    )
    (net (code "67") (name "unconnected-(BUS-Pad9)") (class "Default")
      (node (ref "BUS") (pin "9") (pinfunction "9_9") (pintype "passive"))
    )
    (net (code "68") (name "unconnected-(BUS-Pad10)") (class "Default")
      (node (ref "BUS") (pin "10") (pinfunction "10_10") (pintype "passive"))
    )
    (net (code "69") (name "unconnected-(IC1-ADC6-Pad19)") (class "Default")
      (node (ref "IC1") (pin "19") (pinfunction "ADC6_19") (pintype "passive"))
    )
    (net (code "70") (name "unconnected-(IC1-ADC7-Pad22)") (class "Default")
      (node (ref "IC1") (pin "22") (pinfunction "ADC7_22") (pintype "passive"))
    )
    (net (code "71") (name "unconnected-(IC1-AREF-Pad20)") (class "Default")
      (node (ref "IC1") (pin "20") (pinfunction "AREF_20") (pintype "passive"))
    )
    (net (code "72") (name "unconnected-(ISP-Pad2)") (class "Default")
      (node (ref "ISP") (pin "2") (pinfunction "2_2") (pintype "passive"))
    )
    (net (code "73") (name "unconnected-(ISP-Pad3)") (class "Default")
      (node (ref "ISP") (pin "3") (pinfunction "3_3") (pintype "passive"))
    )
  )
)
